# OPEN_DROP_DIGISCOPE_BOARD_1_v2_RELAYS.net
KiCad netlist of a schematic drawn in EAGLE
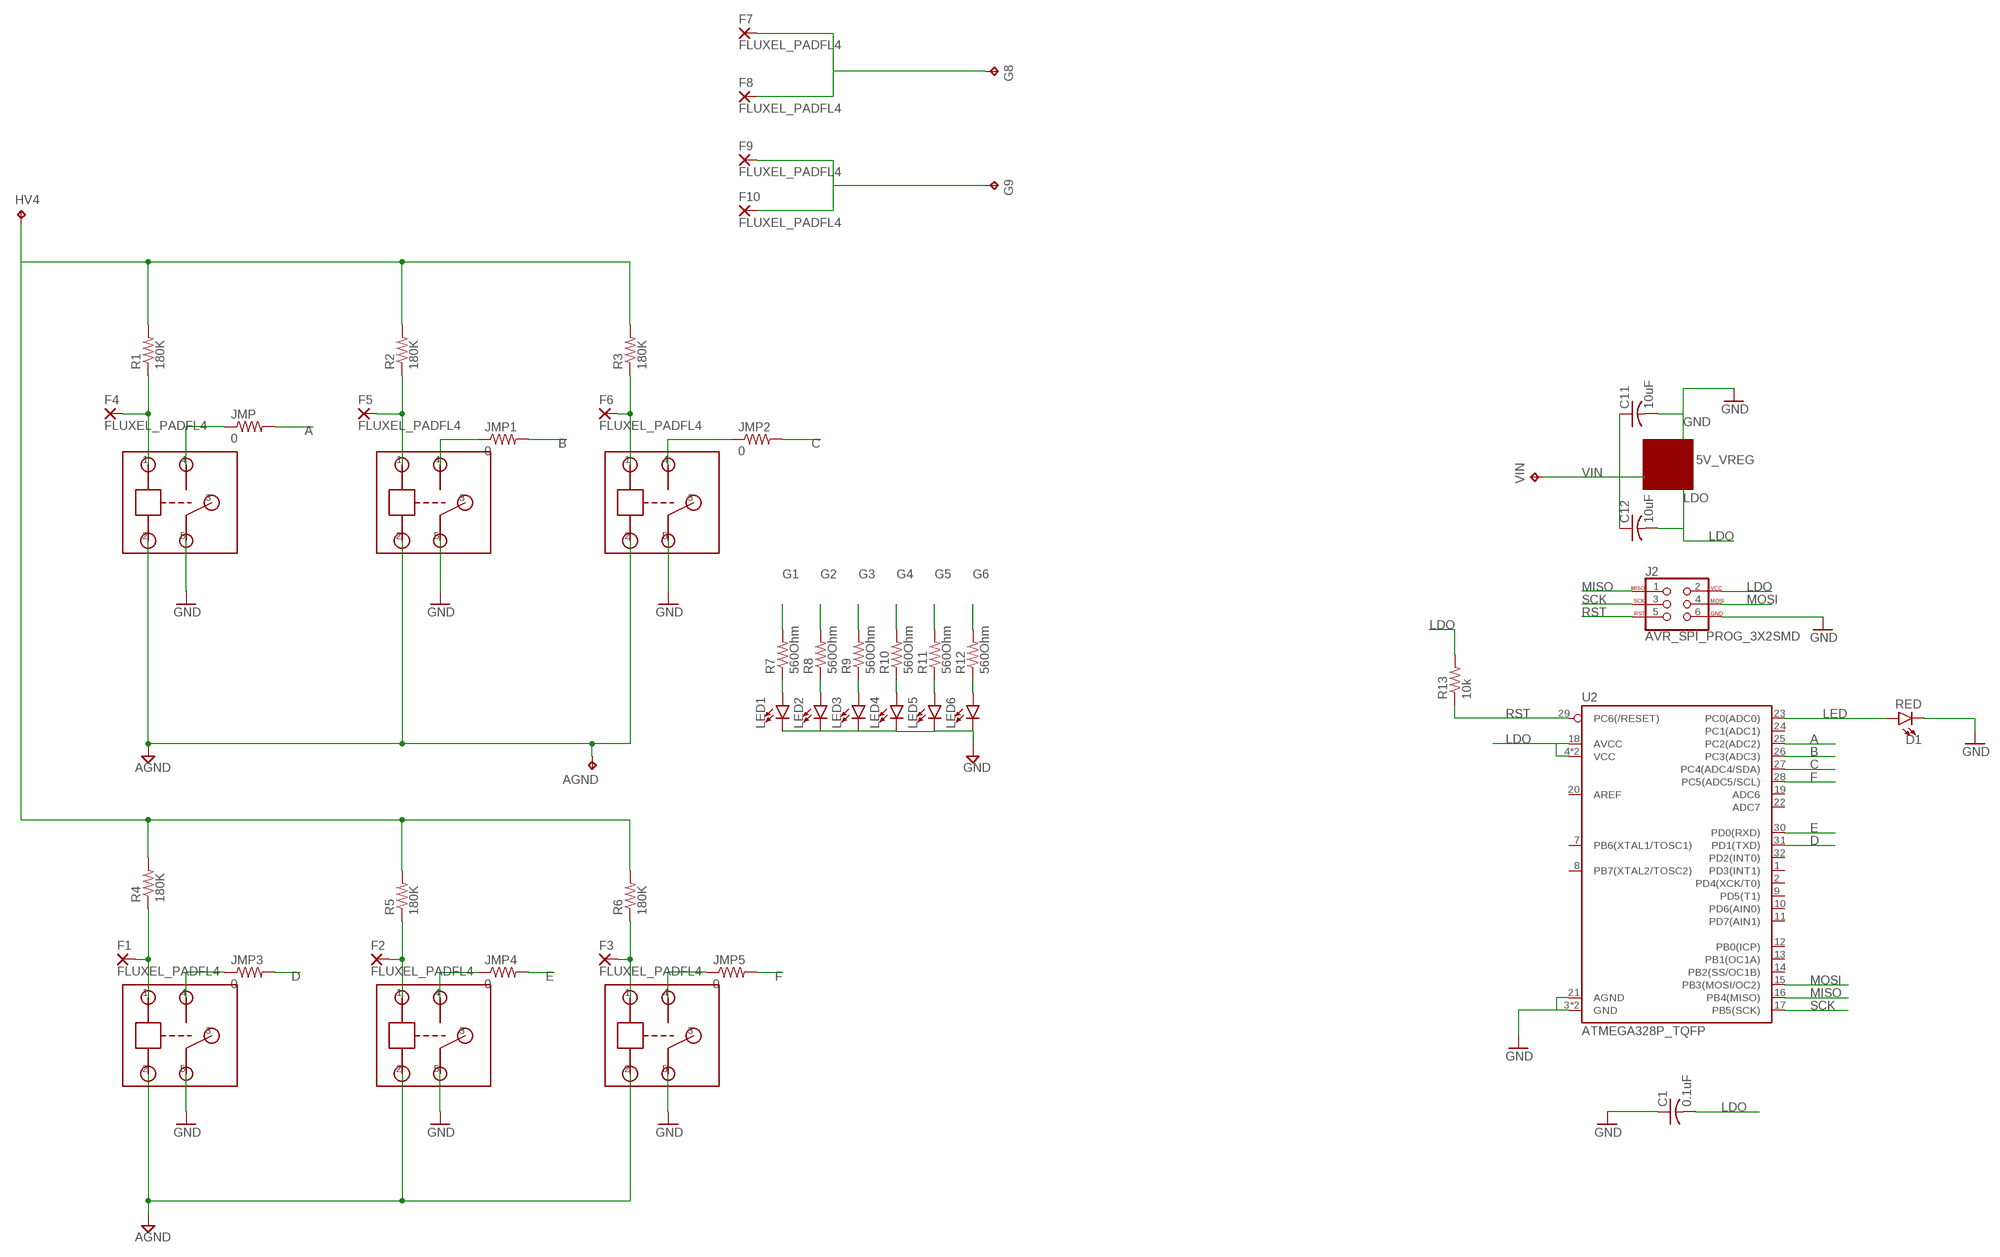
[diagram p0: schematic, sheet 1]

(export (version "E")
  (design (tool "Eeschema 10.0.6"))
  (components
    (comp (ref "5V_VREG")
      (value "MOSFET_PCH-DMG2305UX-7")
      (footprint "eagle-import:SOT23-3")
      (libsource (lib "eagle-import") (part "MOSFET_PCH-DMG2305UX-7"))
    )
    (comp (ref "AGND")
      (value "TPB2,54")
      (footprint "eagle-import:B2,54")
      (libsource (lib "eagle-import") (part "TPB2,54"))
    )
    (comp (ref "C1")
      (value "0.1uF")
      (footprint "eagle-import:C1206")
      (libsource (lib "eagle-import") (part "C-USC1206"))
    )
    (comp (ref "C11")
      (value "10uF")
      (footprint "eagle-import:C1206")
      (libsource (lib "eagle-import") (part "C-USC1206"))
    )
    (comp (ref "C12")
      (value "10uF")
      (footprint "eagle-import:C1206")
      (libsource (lib "eagle-import") (part "C-USC1206"))
    )
    (comp (ref "D1")
      (value "RED")
      (footprint "eagle-import:LED-1206")
      (libsource (lib "eagle-import") (part "LED-RED1206"))
    )
    (comp (ref "F1")
      (value "FLUXEL_PADFL4")
      (footprint "eagle-import:FLUXEL_PAD4")
      (libsource (lib "eagle-import") (part "FLUXEL_PADFL4"))
    )
    (comp (ref "F2")
      (value "FLUXEL_PADFL4")
      (footprint "eagle-import:FLUXEL_PAD4")
      (libsource (lib "eagle-import") (part "FLUXEL_PADFL4"))
    )
    (comp (ref "F3")
      (value "FLUXEL_PADFL4")
      (footprint "eagle-import:FLUXEL_PAD4")
      (libsource (lib "eagle-import") (part "FLUXEL_PADFL4"))
    )
    (comp (ref "F4")
      (value "FLUXEL_PADFL4")
      (footprint "eagle-import:FLUXEL_PAD4")
      (libsource (lib "eagle-import") (part "FLUXEL_PADFL4"))
    )
    (comp (ref "F5")
      (value "FLUXEL_PADFL4")
      (footprint "eagle-import:FLUXEL_PAD4")
      (libsource (lib "eagle-import") (part "FLUXEL_PADFL4"))
    )
    (comp (ref "F6")
      (value "FLUXEL_PADFL4")
      (footprint "eagle-import:FLUXEL_PAD4")
      (libsource (lib "eagle-import") (part "FLUXEL_PADFL4"))
    )
    (comp (ref "F7")
      (value "FLUXEL_PADFL4")
      (footprint "eagle-import:FLUXEL_PAD4")
      (libsource (lib "eagle-import") (part "FLUXEL_PADFL4"))
    )
    (comp (ref "F8")
      (value "FLUXEL_PADFL4")
      (footprint "eagle-import:FLUXEL_PAD4")
      (libsource (lib "eagle-import") (part "FLUXEL_PADFL4"))
    )
    (comp (ref "F9")
      (value "FLUXEL_PADFL4")
      (footprint "eagle-import:FLUXEL_PAD4")
      (libsource (lib "eagle-import") (part "FLUXEL_PADFL4"))
    )
    (comp (ref "F10")
      (value "FLUXEL_PADFL4")
      (footprint "eagle-import:FLUXEL_PAD4")
      (libsource (lib "eagle-import") (part "FLUXEL_PADFL4"))
    )
    (comp (ref "G8")
      (value "TPB2,54")
      (footprint "eagle-import:B2,54")
      (libsource (lib "eagle-import") (part "TPB2,54"))
    )
    (comp (ref "G9")
      (value "TPB2,54")
      (footprint "eagle-import:B2,54")
      (libsource (lib "eagle-import") (part "TPB2,54"))
    )
    (comp (ref "HV4")
      (value "TPB2,54")
      (footprint "eagle-import:B2,54")
      (libsource (lib "eagle-import") (part "TPB2,54"))
    )
    (comp (ref "J2")
      (value "AVR_SPI_PROG_3X2SMD")
      (footprint "eagle-import:2X3_SMT_POSTS")
      (libsource (lib "eagle-import") (part "AVR_SPI_PROG_3X2SMD"))
    )
    (comp (ref "JMP")
      (value "0")
      (footprint "eagle-import:M1206")
      (libsource (lib "eagle-import") (part "R-US_M1206"))
    )
    (comp (ref "JMP1")
      (value "0")
      (footprint "eagle-import:M1206")
      (libsource (lib "eagle-import") (part "R-US_M1206"))
    )
    (comp (ref "JMP2")
      (value "0")
      (footprint "eagle-import:M1206")
      (libsource (lib "eagle-import") (part "R-US_M1206"))
    )
    (comp (ref "JMP3")
      (value "0")
      (footprint "eagle-import:M1206")
      (libsource (lib "eagle-import") (part "R-US_M1206"))
    )
    (comp (ref "JMP4")
      (value "0")
      (footprint "eagle-import:M1206")
      (libsource (lib "eagle-import") (part "R-US_M1206"))
    )
    (comp (ref "JMP5")
      (value "0")
      (footprint "eagle-import:M1206")
      (libsource (lib "eagle-import") (part "R-US_M1206"))
    )
    (comp (ref "LED1")
      (value "LED1206")
      (footprint "eagle-import:LED-1206")
      (libsource (lib "eagle-import") (part "LED1206"))
    )
    (comp (ref "LED2")
      (value "LED1206")
      (footprint "eagle-import:LED-1206")
      (libsource (lib "eagle-import") (part "LED1206"))
    )
    (comp (ref "LED3")
      (value "LED1206")
      (footprint "eagle-import:LED-1206")
      (libsource (lib "eagle-import") (part "LED1206"))
    )
    (comp (ref "LED4")
      (value "LED1206")
      (footprint "eagle-import:LED-1206")
      (libsource (lib "eagle-import") (part "LED1206"))
    )
    (comp (ref "LED5")
      (value "LED1206")
      (footprint "eagle-import:LED-1206")
      (libsource (lib "eagle-import") (part "LED1206"))
    )
    (comp (ref "LED6")
      (value "LED1206")
      (footprint "eagle-import:LED-1206")
      (libsource (lib "eagle-import") (part "LED1206"))
    )
    (comp (ref "R1")
      (value "180K")
      (footprint "eagle-import:M1206")
      (libsource (lib "eagle-import") (part "R-US_M1206"))
    )
    (comp (ref "R2")
      (value "180K")
      (footprint "eagle-import:M1206")
      (libsource (lib "eagle-import") (part "R-US_M1206"))
    )
    (comp (ref "R3")
      (value "180K")
      (footprint "eagle-import:M1206")
      (libsource (lib "eagle-import") (part "R-US_M1206"))
    )
    (comp (ref "R4")
      (value "180K")
      (footprint "eagle-import:M1206")
      (libsource (lib "eagle-import") (part "R-US_M1206"))
    )
    (comp (ref "R5")
      (value "180K")
      (footprint "eagle-import:M1206")
      (libsource (lib "eagle-import") (part "R-US_M1206"))
    )
    (comp (ref "R6")
      (value "180K")
      (footprint "eagle-import:M1206")
      (libsource (lib "eagle-import") (part "R-US_M1206"))
    )
    (comp (ref "R7")
      (value "560Ohm")
      (footprint "eagle-import:M1206")
      (libsource (lib "eagle-import") (part "R-US_M1206"))
    )
    (comp (ref "R8")
      (value "560Ohm")
      (footprint "eagle-import:M1206")
      (libsource (lib "eagle-import") (part "R-US_M1206"))
    )
    (comp (ref "R9")
      (value "560Ohm")
      (footprint "eagle-import:M1206")
      (libsource (lib "eagle-import") (part "R-US_M1206"))
    )
    (comp (ref "R10")
      (value "560Ohm")
      (footprint "eagle-import:M1206")
      (libsource (lib "eagle-import") (part "R-US_M1206"))
    )
    (comp (ref "R11")
      (value "560Ohm")
      (footprint "eagle-import:M1206")
      (libsource (lib "eagle-import") (part "R-US_M1206"))
    )
    (comp (ref "R12")
      (value "560Ohm")
      (footprint "eagle-import:M1206")
      (libsource (lib "eagle-import") (part "R-US_M1206"))
    )
    (comp (ref "R13")
      (value "10k")
      (footprint "eagle-import:R1206")
      (libsource (lib "eagle-import") (part "R-US_R1206"))
    )
    (comp (ref "U$1")
      (value "RELAY")
      (footprint "eagle-import:RELAY")
      (libsource (lib "eagle-import") (part "RELAY"))
    )
    (comp (ref "U$2")
      (value "RELAY")
      (footprint "eagle-import:RELAY")
      (libsource (lib "eagle-import") (part "RELAY"))
    )
    (comp (ref "U$3")
      (value "RELAY")
      (footprint "eagle-import:RELAY")
      (libsource (lib "eagle-import") (part "RELAY"))
    )
    (comp (ref "U$4")
      (value "RELAY")
      (footprint "eagle-import:RELAY")
      (libsource (lib "eagle-import") (part "RELAY"))
    )
    (comp (ref "U$5")
      (value "RELAY")
      (footprint "eagle-import:RELAY")
      (libsource (lib "eagle-import") (part "RELAY"))
    )
    (comp (ref "U$6")
      (value "RELAY")
      (footprint "eagle-import:RELAY")
      (libsource (lib "eagle-import") (part "RELAY"))
    )
    (comp (ref "U2")
      (value "ATMEGA328P_TQFP")
      (footprint "eagle-import:TQFP32-08")
      (libsource (lib "eagle-import") (part "ATMEGA328P_TQFP"))
    )
    (comp (ref "VIN")
      (value "TPB2,54")
      (footprint "eagle-import:B2,54")
      (libsource (lib "eagle-import") (part "TPB2,54"))
    )
  )
  (nets
    (net (code "1") (name "/A") (class "Default")
      (node (ref "JMP") (pin "2") (pinfunction "2_2") (pintype "passive"))
      (node (ref "U2") (pin "25") (pinfunction "PC2(ADC2)_25") (pintype "bidirectional"))
    )
    (net (code "2") (name "/B") (class "Default")
      (node (ref "JMP1") (pin "2") (pinfunction "2_2") (pintype "passive"))
      (node (ref "U2") (pin "26") (pinfunction "PC3(ADC3)_26") (pintype "bidirectional"))
    )
    (net (code "3") (name "/C") (class "Default")
      (node (ref "JMP2") (pin "2") (pinfunction "2_2") (pintype "passive"))
      (node (ref "U2") (pin "27") (pinfunction "PC4(ADC4/SDA)_27") (pintype "bidirectional"))
    )
    (net (code "4") (name "/D") (class "Default")
      (node (ref "JMP3") (pin "2") (pinfunction "2_2") (pintype "passive"))
      (node (ref "U2") (pin "31") (pinfunction "PD1(TXD)_31") (pintype "bidirectional"))
    )
    (net (code "5") (name "/E") (class "Default")
      (node (ref "JMP4") (pin "2") (pinfunction "2_2") (pintype "passive"))
      (node (ref "U2") (pin "30") (pinfunction "PD0(RXD)_30") (pintype "bidirectional"))
    )
    (net (code "6") (name "/F") (class "Default")
      (node (ref "JMP5") (pin "2") (pinfunction "2_2") (pintype "passive"))
      (node (ref "U2") (pin "28") (pinfunction "PC5(ADC5/SCL)_28") (pintype "bidirectional"))
    )
    (net (code "7") (name "/G1") (class "Default")
      (node (ref "JMP3") (pin "1") (pinfunction "1_1") (pintype "passive"))
      (node (ref "R7") (pin "2") (pinfunction "2_2") (pintype "passive"))
      (node (ref "U$6") (pin "4") (pinfunction "COM-OPEN_4") (pintype "bidirectional"))
    )
    (net (code "8") (name "/G2") (class "Default")
      (node (ref "JMP4") (pin "1") (pinfunction "1_1") (pintype "passive"))
      (node (ref "R8") (pin "2") (pinfunction "2_2") (pintype "passive"))
      (node (ref "U$5") (pin "4") (pinfunction "COM-OPEN_4") (pintype "bidirectional"))
    )
    (net (code "9") (name "/G3") (class "Default")
      (node (ref "JMP5") (pin "1") (pinfunction "1_1") (pintype "passive"))
      (node (ref "R9") (pin "2") (pinfunction "2_2") (pintype "passive"))
      (node (ref "U$4") (pin "4") (pinfunction "COM-OPEN_4") (pintype "bidirectional"))
    )
    (net (code "10") (name "/G4") (class "Default")
      (node (ref "JMP") (pin "1") (pinfunction "1_1") (pintype "passive"))
      (node (ref "R10") (pin "2") (pinfunction "2_2") (pintype "passive"))
      (node (ref "U$3") (pin "4") (pinfunction "COM-OPEN_4") (pintype "bidirectional"))
    )
    (net (code "11") (name "/G5") (class "Default")
      (node (ref "JMP1") (pin "1") (pinfunction "1_1") (pintype "passive"))
      (node (ref "R11") (pin "2") (pinfunction "2_2") (pintype "passive"))
      (node (ref "U$2") (pin "4") (pinfunction "COM-OPEN_4") (pintype "bidirectional"))
    )
    (net (code "12") (name "/G6") (class "Default")
      (node (ref "JMP2") (pin "1") (pinfunction "1_1") (pintype "passive"))
      (node (ref "R12") (pin "2") (pinfunction "2_2") (pintype "passive"))
      (node (ref "U$1") (pin "4") (pinfunction "COM-OPEN_4") (pintype "bidirectional"))
    )
    (net (code "13") (name "/LDO") (class "Default")
      (node (ref "5V_VREG") (pin "2") (pinfunction "S_2") (pintype "bidirectional"))
      (node (ref "C1") (pin "2") (pinfunction "2_2") (pintype "passive"))
      (node (ref "C12") (pin "2") (pinfunction "2_2") (pintype "passive"))
      (node (ref "J2") (pin "2") (pinfunction "2_2") (pintype "passive"))
      (node (ref "R13") (pin "2") (pinfunction "2_2") (pintype "passive"))
      (node (ref "U2") (pin "18") (pinfunction "AVCC_18") (pintype "bidirectional"))
      (node (ref "U2") (pin "4") (pinfunction "VCC_4") (pintype "bidirectional"))
      (node (ref "U2") (pin "6") (pinfunction "VCC_6") (pintype "bidirectional"))
    )
    (net (code "14") (name "/LED") (class "Default")
      (node (ref "D1") (pin "A") (pinfunction "A_A") (pintype "passive"))
      (node (ref "U2") (pin "23") (pinfunction "PC0(ADC0)_23") (pintype "bidirectional"))
    )
    (net (code "15") (name "/MISO") (class "Default")
      (node (ref "J2") (pin "1") (pinfunction "1_1") (pintype "passive"))
      (node (ref "U2") (pin "16") (pinfunction "PB4(MISO)_16") (pintype "bidirectional"))
    )
    (net (code "16") (name "/MOSI") (class "Default")
      (node (ref "J2") (pin "4") (pinfunction "4_4") (pintype "passive"))
      (node (ref "U2") (pin "15") (pinfunction "PB3(MOSI/OC2)_15") (pintype "bidirectional"))
    )
    (net (code "17") (name "/RST") (class "Default")
      (node (ref "J2") (pin "5") (pinfunction "5_5") (pintype "passive"))
      (node (ref "R13") (pin "1") (pinfunction "1_1") (pintype "passive"))
      (node (ref "U2") (pin "29") (pinfunction "PC6(/RESET)_29") (pintype "bidirectional"))
    )
    (net (code "18") (name "/SCK") (class "Default")
      (node (ref "J2") (pin "3") (pinfunction "3_3") (pintype "passive"))
      (node (ref "U2") (pin "17") (pinfunction "PB5(SCK)_17") (pintype "bidirectional"))
    )
    (net (code "19") (name "/VIN") (class "Default")
      (node (ref "5V_VREG") (pin "1") (pinfunction "G_1") (pintype "bidirectional"))
      (node (ref "C11") (pin "1") (pinfunction "1_1") (pintype "passive"))
      (node (ref "C12") (pin "1") (pinfunction "1_1") (pintype "passive"))
      (node (ref "VIN") (pin "TP") (pinfunction "TP_TP") (pintype "input"))
    )
    (net (code "20") (name "AGND") (class "Default")
      (node (ref "AGND") (pin "TP") (pinfunction "TP_TP") (pintype "input"))
      (node (ref "U$1") (pin "2") (pinfunction "GND_2") (pintype "bidirectional"))
      (node (ref "U$2") (pin "2") (pinfunction "GND_2") (pintype "bidirectional"))
      (node (ref "U$3") (pin "2") (pinfunction "GND_2") (pintype "bidirectional"))
      (node (ref "U$4") (pin "2") (pinfunction "GND_2") (pintype "bidirectional"))
      (node (ref "U$5") (pin "2") (pinfunction "GND_2") (pintype "bidirectional"))
      (node (ref "U$6") (pin "2") (pinfunction "GND_2") (pintype "bidirectional"))
    )
    (net (code "21") (name "GND") (class "Default")
      (node (ref "5V_VREG") (pin "3") (pinfunction "D_3") (pintype "bidirectional"))
      (node (ref "C1") (pin "1") (pinfunction "1_1") (pintype "passive"))
      (node (ref "C11") (pin "2") (pinfunction "2_2") (pintype "passive"))
      (node (ref "D1") (pin "C") (pinfunction "C_C") (pintype "passive"))
      (node (ref "J2") (pin "6") (pinfunction "6_6") (pintype "passive"))
      (node (ref "LED1") (pin "C") (pinfunction "C_C") (pintype "passive"))
      (node (ref "LED2") (pin "C") (pinfunction "C_C") (pintype "passive"))
      (node (ref "LED3") (pin "C") (pinfunction "C_C") (pintype "passive"))
      (node (ref "LED4") (pin "C") (pinfunction "C_C") (pintype "passive"))
      (node (ref "LED5") (pin "C") (pinfunction "C_C") (pintype "passive"))
      (node (ref "LED6") (pin "C") (pinfunction "C_C") (pintype "passive"))
      (node (ref "U$1") (pin "5") (pinfunction "COM-CLOSE_5") (pintype "bidirectional"))
      (node (ref "U$2") (pin "5") (pinfunction "COM-CLOSE_5") (pintype "bidirectional"))
      (node (ref "U$3") (pin "5") (pinfunction "COM-CLOSE_5") (pintype "bidirectional"))
      (node (ref "U$4") (pin "5") (pinfunction "COM-CLOSE_5") (pintype "bidirectional"))
      (node (ref "U$5") (pin "5") (pinfunction "COM-CLOSE_5") (pintype "bidirectional"))
      (node (ref "U$6") (pin "5") (pinfunction "COM-CLOSE_5") (pintype "bidirectional"))
      (node (ref "U2") (pin "21") (pinfunction "AGND_21") (pintype "bidirectional"))
      (node (ref "U2") (pin "3") (pinfunction "GND_3") (pintype "bidirectional"))
      (node (ref "U2") (pin "5") (pinfunction "GND_5") (pintype "bidirectional"))
    )
    (net (code "22") (name "Net-(F1-P)") (class "Default")
      (node (ref "F1") (pin "1") (pinfunction "P_1") (pintype "passive"))
      (node (ref "R4") (pin "1") (pinfunction "1_1") (pintype "passive"))
      (node (ref "U$6") (pin "1") (pinfunction "IN_1") (pintype "bidirectional"))
    )
    (net (code "23") (name "Net-(F2-P)") (class "Default")
      (node (ref "F2") (pin "1") (pinfunction "P_1") (pintype "passive"))
      (node (ref "R5") (pin "1") (pinfunction "1_1") (pintype "passive"))
      (node (ref "U$5") (pin "1") (pinfunction "IN_1") (pintype "bidirectional"))
    )
    (net (code "24") (name "Net-(F3-P)") (class "Default")
      (node (ref "F3") (pin "1") (pinfunction "P_1") (pintype "passive"))
      (node (ref "R6") (pin "1") (pinfunction "1_1") (pintype "passive"))
      (node (ref "U$4") (pin "1") (pinfunction "IN_1") (pintype "bidirectional"))
    )
    (net (code "25") (name "Net-(F4-P)") (class "Default")
      (node (ref "F4") (pin "1") (pinfunction "P_1") (pintype "passive"))
      (node (ref "R1") (pin "1") (pinfunction "1_1") (pintype "passive"))
      (node (ref "U$3") (pin "1") (pinfunction "IN_1") (pintype "bidirectional"))
    )
    (net (code "26") (name "Net-(F5-P)") (class "Default")
      (node (ref "F5") (pin "1") (pinfunction "P_1") (pintype "passive"))
      (node (ref "R2") (pin "1") (pinfunction "1_1") (pintype "passive"))
      (node (ref "U$2") (pin "1") (pinfunction "IN_1") (pintype "bidirectional"))
    )
    (net (code "27") (name "Net-(F6-P)") (class "Default")
      (node (ref "F6") (pin "1") (pinfunction "P_1") (pintype "passive"))
      (node (ref "R3") (pin "1") (pinfunction "1_1") (pintype "passive"))
      (node (ref "U$1") (pin "1") (pinfunction "IN_1") (pintype "bidirectional"))
    )
    (net (code "28") (name "Net-(F7-P)") (class "Default")
      (node (ref "F7") (pin "1") (pinfunction "P_1") (pintype "passive"))
      (node (ref "F8") (pin "1") (pinfunction "P_1") (pintype "passive"))
      (node (ref "G8") (pin "TP") (pinfunction "TP_TP") (pintype "input"))
    )
    (net (code "29") (name "Net-(F10-P)") (class "Default")
      (node (ref "F10") (pin "1") (pinfunction "P_1") (pintype "passive"))
      (node (ref "F9") (pin "1") (pinfunction "P_1") (pintype "passive"))
      (node (ref "G9") (pin "TP") (pinfunction "TP_TP") (pintype "input"))
    )
    (net (code "30") (name "Net-(HV4-PadTP)") (class "Default")
      (node (ref "HV4") (pin "TP") (pinfunction "TP_TP") (pintype "input"))
      (node (ref "R1") (pin "2") (pinfunction "2_2") (pintype "passive"))
      (node (ref "R2") (pin "2") (pinfunction "2_2") (pintype "passive"))
      (node (ref "R3") (pin "2") (pinfunction "2_2") (pintype "passive"))
      (node (ref "R4") (pin "2") (pinfunction "2_2") (pintype "passive"))
      (node (ref "R5") (pin "2") (pinfunction "2_2") (pintype "passive"))
      (node (ref "R6") (pin "2") (pinfunction "2_2") (pintype "passive"))
    )
    (net (code "31") (name "Net-(LED1-PadA)") (class "Default")
      (node (ref "LED1") (pin "A") (pinfunction "A_A") (pintype "passive"))
      (node (ref "R7") (pin "1") (pinfunction "1_1") (pintype "passive"))
    )
    (net (code "32") (name "Net-(LED2-PadA)") (class "Default")
      (node (ref "LED2") (pin "A") (pinfunction "A_A") (pintype "passive"))
      (node (ref "R8") (pin "1") (pinfunction "1_1") (pintype "passive"))
    )
    (net (code "33") (name "Net-(LED3-PadA)") (class "Default")
      (node (ref "LED3") (pin "A") (pinfunction "A_A") (pintype "passive"))
      (node (ref "R9") (pin "1") (pinfunction "1_1") (pintype "passive"))
    )
    (net (code "34") (name "Net-(LED4-PadA)") (class "Default")
      (node (ref "LED4") (pin "A") (pinfunction "A_A") (pintype "passive"))
      (node (ref "R10") (pin "1") (pinfunction "1_1") (pintype "passive"))
    )
    (net (code "35") (name "Net-(LED5-PadA)") (class "Default")
      (node (ref "LED5") (pin "A") (pinfunction "A_A") (pintype "passive"))
      (node (ref "R11") (pin "1") (pinfunction "1_1") (pintype "passive"))
    )
    (net (code "36") (name "Net-(LED6-PadA)") (class "Default")
      (node (ref "LED6") (pin "A") (pinfunction "A_A") (pintype "passive"))
      (node (ref "R12") (pin "1") (pinfunction "1_1") (pintype "passive"))
    )
    (net (code "37") (name "unconnected-(U$1-COM-Pad3)") (class "Default")
      (node (ref "U$1") (pin "3") (pinfunction "COM_3") (pintype "bidirectional"))
    )
    (net (code "38") (name "unconnected-(U$2-COM-Pad3)") (class "Default")
      (node (ref "U$2") (pin "3") (pinfunction "COM_3") (pintype "bidirectional"))
    )
    (net (code "39") (name "unconnected-(U$3-COM-Pad3)") (class "Default")
      (node (ref "U$3") (pin "3") (pinfunction "COM_3") (pintype "bidirectional"))
    )
    (net (code "40") (name "unconnected-(U$4-COM-Pad3)") (class "Default")
      (node (ref "U$4") (pin "3") (pinfunction "COM_3") (pintype "bidirectional"))
    )
    (net (code "41") (name "unconnected-(U$5-COM-Pad3)") (class "Default")
      (node (ref "U$5") (pin "3") (pinfunction "COM_3") (pintype "bidirectional"))
    )
    (net (code "42") (name "unconnected-(U$6-COM-Pad3)") (class "Default")
      (node (ref "U$6") (pin "3") (pinfunction "COM_3") (pintype "bidirectional"))
    )
    (net (code "43") (name "unconnected-(U2-ADC6-Pad19)") (class "Default")
      (node (ref "U2") (pin "19") (pinfunction "ADC6_19") (pintype "bidirectional"))
    )
    (net (code "44") (name "unconnected-(U2-ADC7-Pad22)") (class "Default")
      (node (ref "U2") (pin "22") (pinfunction "ADC7_22") (pintype "bidirectional"))
    )
    (net (code "45") (name "unconnected-(U2-AREF-Pad20)") (class "Default")
      (node (ref "U2") (pin "20") (pinfunction "AREF_20") (pintype "bidirectional"))
    )
    (net (code "46") (name "unconnected-(U2-PB0(ICP)-Pad12)") (class "Default")
      (node (ref "U2") (pin "12") (pinfunction "PB0(ICP)_12") (pintype "bidirectional"))
    )
    (net (code "47") (name "unconnected-(U2-PB1(OC1A)-Pad13)") (class "Default")
      (node (ref "U2") (pin "13") (pinfunction "PB1(OC1A)_13") (pintype "bidirectional"))
    )
    (net (code "48") (name "unconnected-(U2-PB2(SS{slash}OC1B)-Pad14)") (class "Default")
      (node (ref "U2") (pin "14") (pinfunction "PB2(SS/OC1B)_14") (pintype "bidirectional"))
    )
    (net (code "49") (name "unconnected-(U2-PB6(XTAL1{slash}TOSC1)-Pad7)") (class "Default")
      (node (ref "U2") (pin "7") (pinfunction "PB6(XTAL1/TOSC1)_7") (pintype "bidirectional"))
    )
    (net (code "50") (name "unconnected-(U2-PB7(XTAL2{slash}TOSC2)-Pad8)") (class "Default")
      (node (ref "U2") (pin "8") (pinfunction "PB7(XTAL2/TOSC2)_8") (pintype "bidirectional"))
    )
    (net (code "51") (name "unconnected-(U2-PC1(ADC1)-Pad24)") (class "Default")
      (node (ref "U2") (pin "24") (pinfunction "PC1(ADC1)_24") (pintype "bidirectional"))
    )
    (net (code "52") (name "unconnected-(U2-PD2(INT0)-Pad32)") (class "Default")
      (node (ref "U2") (pin "32") (pinfunction "PD2(INT0)_32") (pintype "bidirectional"))
    )
    (net (code "53") (name "unconnected-(U2-PD3(INT1)-Pad1)") (class "Default")
      (node (ref "U2") (pin "1") (pinfunction "PD3(INT1)_1") (pintype "bidirectional"))
    )
    (net (code "54") (name "unconnected-(U2-PD4(XCK{slash}T0)-Pad2)") (class "Default")
      (node (ref "U2") (pin "2") (pinfunction "PD4(XCK/T0)_2") (pintype "bidirectional"))
    )
    (net (code "55") (name "unconnected-(U2-PD5(T1)-Pad9)") (class "Default")
      (node (ref "U2") (pin "9") (pinfunction "PD5(T1)_9") (pintype "bidirectional"))
    )
    (net (code "56") (name "unconnected-(U2-PD6(AIN0)-Pad10)") (class "Default")
      (node (ref "U2") (pin "10") (pinfunction "PD6(AIN0)_10") (pintype "bidirectional"))
    )
    (net (code "57") (name "unconnected-(U2-PD7(AIN1)-Pad11)") (class "Default")
      (node (ref "U2") (pin "11") (pinfunction "PD7(AIN1)_11") (pintype "bidirectional"))
    )
  )
)
